# thermometer.net
KiCad netlist of a schematic drawn in EAGLE
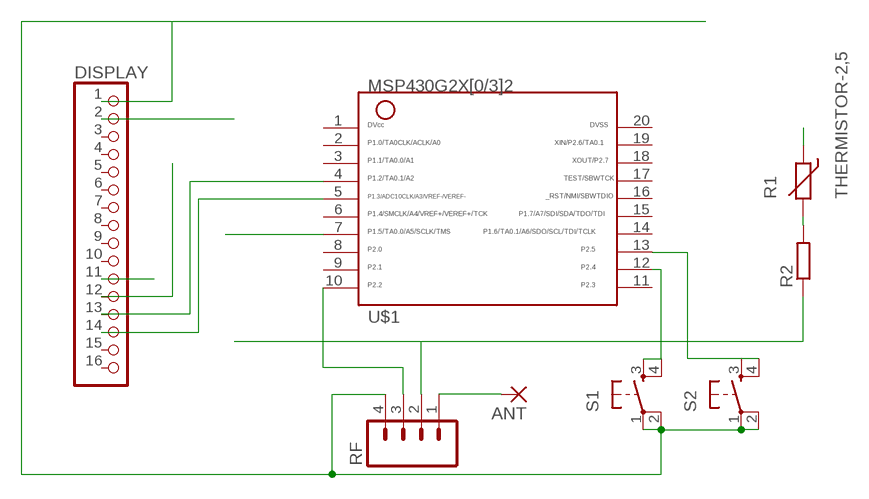
[diagram p0: schematic, sheet 1]

(export (version "E")
  (design (tool "Eeschema 10.0.6"))
  (components
    (comp (ref "ANT")
      (value "2,54/0,9")
      (footprint "eagle-import:2,54_0,9")
      (libsource (lib "eagle-import") (part "2,54/0,9"))
    )
    (comp (ref "DISPLAY")
      (value "PINHD-1X16")
      (footprint "eagle-import:1X16")
      (libsource (lib "eagle-import") (part "PINHD-1X16"))
    )
    (comp (ref "R1")
      (value "THERMISTOR-2,5")
      (footprint "eagle-import:RS-2,5")
      (libsource (lib "eagle-import") (part "THERMISTOR-2,5"))
    )
    (comp (ref "R2")
      (value "R-EU_0207/10")
      (footprint "eagle-import:0207_10")
      (libsource (lib "eagle-import") (part "R-EU_0207/10"))
    )
    (comp (ref "RF")
      (value "M04PTH")
      (footprint "eagle-import:1X04")
      (libsource (lib "eagle-import") (part "M04PTH"))
    )
    (comp (ref "S1")
      (value "TAC_SWITCHPTH")
      (footprint "eagle-import:TACTILE-PTH")
      (libsource (lib "eagle-import") (part "TAC_SWITCHPTH"))
    )
    (comp (ref "S2")
      (value "TAC_SWITCHPTH")
      (footprint "eagle-import:TACTILE-PTH")
      (libsource (lib "eagle-import") (part "TAC_SWITCHPTH"))
    )
    (comp (ref "U$1")
      (value "G2X[0/3]2---N20")
      (footprint "eagle-import:N20")
      (libsource (lib "eagle-import") (part "G2X[0/3]2---N20"))
    )
  )
  (nets
    (net (code "1") (name "Net-(ANT-P)") (class "Default")
      (node (ref "ANT") (pin "1") (pinfunction "P_1") (pintype "passive"))
      (node (ref "RF") (pin "1") (pinfunction "1_1") (pintype "passive"))
    )
    (net (code "2") (name "Net-(DISPLAY-Pad1)") (class "Default")
      (node (ref "DISPLAY") (pin "1") (pinfunction "1_1") (pintype "passive"))
      (node (ref "RF") (pin "4") (pinfunction "4_4") (pintype "passive"))
      (node (ref "S1") (pin "1") (pinfunction "1_1") (pintype "passive"))
      (node (ref "S1") (pin "2") (pinfunction "2_2") (pintype "passive"))
      (node (ref "S2") (pin "1") (pinfunction "1_1") (pintype "passive"))
      (node (ref "S2") (pin "2") (pinfunction "2_2") (pintype "passive"))
    )
    (net (code "3") (name "Net-(DISPLAY-Pad13)") (class "Default")
      (node (ref "DISPLAY") (pin "13") (pinfunction "13_13") (pintype "passive"))
      (node (ref "U$1") (pin "4") (pinfunction "4_4") (pintype "bidirectional"))
    )
    (net (code "4") (name "Net-(DISPLAY-Pad14)") (class "Default")
      (node (ref "DISPLAY") (pin "14") (pinfunction "14_14") (pintype "passive"))
      (node (ref "U$1") (pin "5") (pinfunction "5_5") (pintype "bidirectional"))
    )
    (net (code "5") (name "Net-(R1-Pad2)") (class "Default")
      (node (ref "R1") (pin "2") (pinfunction "2_2") (pintype "passive"))
      (node (ref "R2") (pin "2") (pinfunction "2_2") (pintype "passive"))
    )
    (net (code "6") (name "Net-(R2-Pad1)") (class "Default")
      (node (ref "R2") (pin "1") (pinfunction "1_1") (pintype "passive"))
      (node (ref "RF") (pin "2") (pinfunction "2_2") (pintype "passive"))
    )
    (net (code "7") (name "Net-(RF-Pad3)") (class "Default")
      (node (ref "RF") (pin "3") (pinfunction "3_3") (pintype "passive"))
      (node (ref "U$1") (pin "10") (pinfunction "10_10") (pintype "bidirectional"))
    )
    (net (code "8") (name "Net-(S1-Pad3)") (class "Default")
      (node (ref "S1") (pin "3") (pinfunction "3_3") (pintype "passive"))
      (node (ref "S1") (pin "4") (pinfunction "4_4") (pintype "passive"))
      (node (ref "U$1") (pin "12") (pinfunction "12_12") (pintype "bidirectional"))
    )
    (net (code "9") (name "Net-(S2-Pad3)") (class "Default")
      (node (ref "S2") (pin "3") (pinfunction "3_3") (pintype "passive"))
      (node (ref "S2") (pin "4") (pinfunction "4_4") (pintype "passive"))
      (node (ref "U$1") (pin "13") (pinfunction "13_13") (pintype "bidirectional"))
    )
    (net (code "10") (name "unconnected-(DISPLAY-Pad2)") (class "Default")
      (node (ref "DISPLAY") (pin "2") (pinfunction "2_2") (pintype "passive"))
    )
    (net (code "11") (name "unconnected-(DISPLAY-Pad3)") (class "Default")
      (node (ref "DISPLAY") (pin "3") (pinfunction "3_3") (pintype "passive"))
    )
    (net (code "12") (name "unconnected-(DISPLAY-Pad4)") (class "Default")
      (node (ref "DISPLAY") (pin "4") (pinfunction "4_4") (pintype "passive"))
    )
    (net (code "13") (name "unconnected-(DISPLAY-Pad5)") (class "Default")
      (node (ref "DISPLAY") (pin "5") (pinfunction "5_5") (pintype "passive"))
    )
    (net (code "14") (name "unconnected-(DISPLAY-Pad6)") (class "Default")
      (node (ref "DISPLAY") (pin "6") (pinfunction "6_6") (pintype "passive"))
    )
    (net (code "15") (name "unconnected-(DISPLAY-Pad7)") (class "Default")
      (node (ref "DISPLAY") (pin "7") (pinfunction "7_7") (pintype "passive"))
    )
    (net (code "16") (name "unconnected-(DISPLAY-Pad8)") (class "Default")
      (node (ref "DISPLAY") (pin "8") (pinfunction "8_8") (pintype "passive"))
    )
    (net (code "17") (name "unconnected-(DISPLAY-Pad9)") (class "Default")
      (node (ref "DISPLAY") (pin "9") (pinfunction "9_9") (pintype "passive"))
    )
    (net (code "18") (name "unconnected-(DISPLAY-Pad10)") (class "Default")
      (node (ref "DISPLAY") (pin "10") (pinfunction "10_10") (pintype "passive"))
    )
    (net (code "19") (name "unconnected-(DISPLAY-Pad11)") (class "Default")
      (node (ref "DISPLAY") (pin "11") (pinfunction "11_11") (pintype "passive"))
    )
    (net (code "20") (name "unconnected-(DISPLAY-Pad12)") (class "Default")
      (node (ref "DISPLAY") (pin "12") (pinfunction "12_12") (pintype "passive"))
    )
    (net (code "21") (name "unconnected-(DISPLAY-Pad15)") (class "Default")
      (node (ref "DISPLAY") (pin "15") (pinfunction "15_15") (pintype "passive"))
    )
    (net (code "22") (name "unconnected-(DISPLAY-Pad16)") (class "Default")
      (node (ref "DISPLAY") (pin "16") (pinfunction "16_16") (pintype "passive"))
    )
    (net (code "23") (name "unconnected-(R1-Pad1)") (class "Default")
      (node (ref "R1") (pin "1") (pinfunction "1_1") (pintype "passive"))
    )
    (net (code "24") (name "unconnected-(U$1-Pad1)") (class "Default")
      (node (ref "U$1") (pin "1") (pinfunction "1_1") (pintype "bidirectional"))
    )
    (net (code "25") (name "unconnected-(U$1-Pad2)") (class "Default")
      (node (ref "U$1") (pin "2") (pinfunction "2_2") (pintype "bidirectional"))
    )
    (net (code "26") (name "unconnected-(U$1-Pad3)") (class "Default")
      (node (ref "U$1") (pin "3") (pinfunction "3_3") (pintype "bidirectional"))
    )
    (net (code "27") (name "unconnected-(U$1-Pad6)") (class "Default")
      (node (ref "U$1") (pin "6") (pinfunction "6_6") (pintype "bidirectional"))
    )
    (net (code "28") (name "unconnected-(U$1-Pad7)") (class "Default")
      (node (ref "U$1") (pin "7") (pinfunction "7_7") (pintype "bidirectional"))
    )
    (net (code "29") (name "unconnected-(U$1-Pad8)") (class "Default")
      (node (ref "U$1") (pin "8") (pinfunction "8_8") (pintype "bidirectional"))
    )
    (net (code "30") (name "unconnected-(U$1-Pad9)") (class "Default")
      (node (ref "U$1") (pin "9") (pinfunction "9_9") (pintype "bidirectional"))
    )
    (net (code "31") (name "unconnected-(U$1-Pad11)") (class "Default")
      (node (ref "U$1") (pin "11") (pinfunction "11_11") (pintype "bidirectional"))
    )
    (net (code "32") (name "unconnected-(U$1-Pad14)") (class "Default")
      (node (ref "U$1") (pin "14") (pinfunction "14_14") (pintype "bidirectional"))
    )
    (net (code "33") (name "unconnected-(U$1-Pad15)") (class "Default")
      (node (ref "U$1") (pin "15") (pinfunction "15_15") (pintype "bidirectional"))
    )
    (net (code "34") (name "unconnected-(U$1-Pad16)") (class "Default")
      (node (ref "U$1") (pin "16") (pinfunction "16_16") (pintype "bidirectional"))
    )
    (net (code "35") (name "unconnected-(U$1-Pad17)") (class "Default")
      (node (ref "U$1") (pin "17") (pinfunction "17_17") (pintype "bidirectional"))
    )
    (net (code "36") (name "unconnected-(U$1-Pad18)") (class "Default")
      (node (ref "U$1") (pin "18") (pinfunction "18_18") (pintype "bidirectional"))
    )
    (net (code "37") (name "unconnected-(U$1-Pad19)") (class "Default")
      (node (ref "U$1") (pin "19") (pinfunction "19_19") (pintype "bidirectional"))
    )
    (net (code "38") (name "unconnected-(U$1-Pad20)") (class "Default")
      (node (ref "U$1") (pin "20") (pinfunction "20_20") (pintype "bidirectional"))
    )
  )
)
